# CAN.net
KiCad netlist of a schematic drawn in Altium Designer
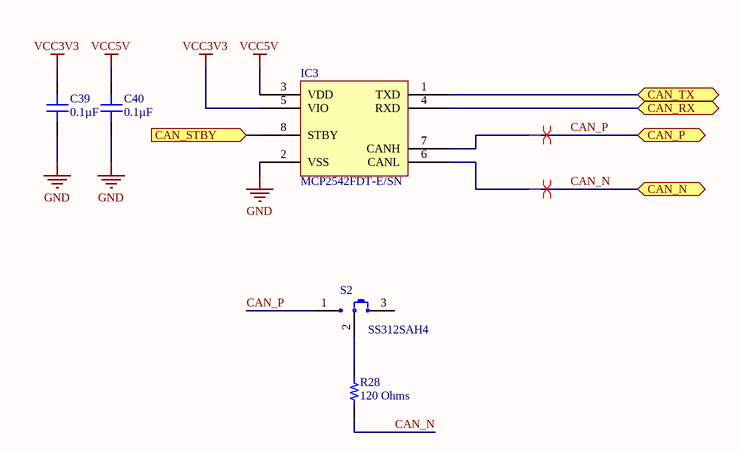
[diagram p0: CAN.SchDoc]

(export (version "E")
  (design (tool "Eeschema 10.0.6"))
  (components
    (comp (ref "C39")
      (value "0.1µF")
      (footprint "CAP 0201_0603")
      (description "CAP CER 0.1UF 16V X5R 0201")
      (fields (field (name "PART NUMBER") "EMK063BJ104KP-F") (field (name "MANUFACTURER") "Taiyo Yuden"))
      (libsource (lib "Celestial") (part "Capacitor"))
    )
    (comp (ref "C40")
      (value "0.1µF")
      (footprint "CAP 0201_0603")
      (description "CAP CER 0.1UF 16V X5R 0201")
      (fields (field (name "PART NUMBER") "EMK063BJ104KP-F") (field (name "MANUFACTURER") "Taiyo Yuden"))
      (libsource (lib "Celestial") (part "Capacitor"))
    )
    (comp (ref "IC3")
      (value "MCP2542FDT-E/SN")
      (footprint "MICROCHIP SOIC-8 150MIL WIDE")
      (description "IC TRANSCEIVER 1/1 8SOIC")
      (fields (field (name "MANUFACTURER") "Microchip Technology"))
      (libsource (lib "Celestial") (part "MICROCHIP MCP2542FD"))
    )
    (comp (ref "R28")
      (value "120 Ohms")
      (footprint "RES 0402_1005")
      (description "RES SMD 120 OHM 5% 1/16W 0402")
      (fields (field (name "PART NUMBER") "RC0402JR-07120RL") (field (name "MANUFACTURER") "Yageo"))
      (libsource (lib "CAL") (part "Resistor"))
    )
    (comp (ref "S2")
      (value "SS312SAH4")
      (footprint "NKK SS312SAH4")
      (description "SWITCH SLIDE SPDT 0.4VA 28V")
      (fields (field (name "MANUFACTURER") "NKK Switches"))
      (libsource (lib "CAL") (part "NKK SS312"))
    )
  )
  (nets
    (net (code "1") (name "/CAN_N") (class "Default")
      (node (ref "IC3") (pin "6") (pinfunction "CANL_6") (pintype "passive"))
      (node (ref "R28") (pin "1") (pinfunction "1_1") (pintype "passive"))
    )
    (net (code "2") (name "/CAN_P") (class "Default")
      (node (ref "IC3") (pin "7") (pinfunction "CANH_7") (pintype "passive"))
      (node (ref "S2") (pin "1") (pinfunction "1_1") (pintype "passive"))
    )
    (net (code "3") (name "/CAN_RX") (class "Default")
      (node (ref "IC3") (pin "4") (pinfunction "RXD_4") (pintype "passive"))
    )
    (net (code "4") (name "/CAN_STBY") (class "Default")
      (node (ref "IC3") (pin "8") (pinfunction "STBY_8") (pintype "passive"))
    )
    (net (code "5") (name "/CAN_TX") (class "Default")
      (node (ref "IC3") (pin "1") (pinfunction "TXD_1") (pintype "passive"))
    )
    (net (code "6") (name "GND") (class "Default")
      (node (ref "C39") (pin "1") (pinfunction "1_1") (pintype "passive"))
      (node (ref "C40") (pin "1") (pinfunction "1_1") (pintype "passive"))
      (node (ref "IC3") (pin "2") (pinfunction "VSS_2") (pintype "passive"))
    )
    (net (code "7") (name "Net-(S2-COM)") (class "Default")
      (node (ref "R28") (pin "2") (pinfunction "2_2") (pintype "passive"))
      (node (ref "S2") (pin "2") (pinfunction "COM_2") (pintype "passive"))
    )
    (net (code "8") (name "VCC3V3") (class "Default")
      (node (ref "C39") (pin "2") (pinfunction "2_2") (pintype "passive"))
      (node (ref "IC3") (pin "5") (pinfunction "VIO_5") (pintype "passive"))
    )
    (net (code "9") (name "VCC5V") (class "Default")
      (node (ref "C40") (pin "2") (pinfunction "2_2") (pintype "passive"))
      (node (ref "IC3") (pin "3") (pinfunction "VDD_3") (pintype "passive"))
    )
    (net (code "10") (name "unconnected-(S2-Pad3)") (class "Default")
      (node (ref "S2") (pin "3") (pinfunction "3_3") (pintype "passive"))
    )
  )
)
